# USB2TTL.net
KiCad netlist of a schematic drawn in Altium Designer
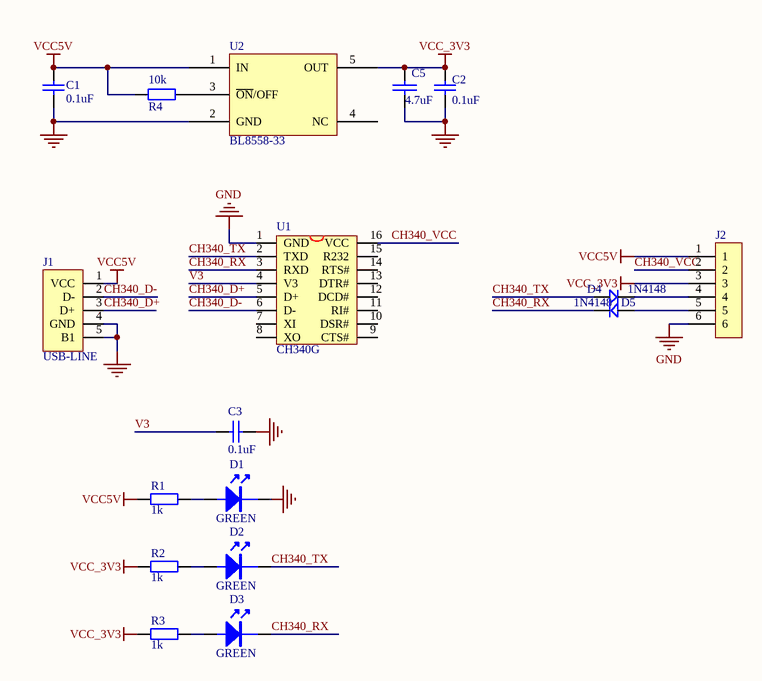
[diagram p0: USB2TTL.SchDoc]

(export (version "E")
  (design (tool "Eeschema 10.0.6"))
  (components
    (comp (ref "C1")
      (value "0.1uF")
      (footprint "FT_0603_C")
      (description "CAP CER .1UF 16V 10% X7R 0603")
      (fields
        (field (name "PART NUMBER") "GRM188R71C104KA01D")
        (field (name "MANUFACTURER") "Murata Electronics North America")
      )
      (libsource (lib "Altium_SVN_Library") (part "Capacitor"))
    )
    (comp (ref "C2")
      (value "0.1uF")
      (footprint "FT_0603_C")
      (description "CAP CER .1UF 16V 10% X7R 0603")
      (fields
        (field (name "PART NUMBER") "GRM188R71C104KA01D")
        (field (name "MANUFACTURER") "Murata Electronics North America")
      )
      (libsource (lib "Altium_SVN_Library") (part "Capacitor"))
    )
    (comp (ref "C3")
      (value "0.1uF")
      (footprint "FT_0603_C")
      (description "CAP CER .1UF 16V 10% X7R 0603")
      (fields
        (field (name "PART NUMBER") "GRM188R71C104KA01D")
        (field (name "MANUFACTURER") "Murata Electronics North America")
      )
      (libsource (lib "Altium_SVN_Library") (part "Capacitor"))
    )
    (comp (ref "C5")
      (value "4.7uF")
      (footprint "FT_0805_C")
      (description "Capacitor")
      (libsource (lib "*") (part "CAP"))
    )
    (comp (ref "D1") (value "GREEN") (footprint "FT_0603_D") (libsource (lib "FTSCH") (part "LED")))
    (comp (ref "D2") (value "GREEN") (footprint "FT_0603_D") (libsource (lib "FTSCH") (part "LED")))
    (comp (ref "D3") (value "GREEN") (footprint "FT_0603_D") (libsource (lib "FTSCH") (part "LED")))
    (comp (ref "D4") (value "1N4148") (footprint "DIODE_SOP") (libsource (lib "WARSHIP") (part "D")))
    (comp (ref "D5") (value "1N4148") (footprint "DIODE_SOP") (libsource (lib "WARSHIP") (part "D")))
    (comp (ref "J1")
      (value "USB-LINE")
      (footprint "FT_USBIF_Micro_BT_CB")
      (libsource (lib "USB转TTL") (part "USB-LINE"))
    )
    (comp (ref "J2") (value "CON6") (footprint "HDR1X6") (libsource (lib "FTSCH") (part "CON6")))
    (comp (ref "R1")
      (value "1k")
      (footprint "FT_0603_R")
      (description "RES 1.0M OHM 1/10W 5% 0603 SMD")
      (fields (field (name "PART NUMBER") "RC0603JR-071ML") (field (name "MANUFACTURER") "Yageo"))
      (libsource (lib "*") (part "Resistor"))
    )
    (comp (ref "R2")
      (value "1k")
      (footprint "FT_0603_R")
      (description "RES 1.0M OHM 1/10W 5% 0603 SMD")
      (fields (field (name "PART NUMBER") "RC0603JR-071ML") (field (name "MANUFACTURER") "Yageo"))
      (libsource (lib "*") (part "Resistor"))
    )
    (comp (ref "R3")
      (value "1k")
      (footprint "FT_0603_R")
      (description "RES 1.0M OHM 1/10W 5% 0603 SMD")
      (fields (field (name "PART NUMBER") "RC0603JR-071ML") (field (name "MANUFACTURER") "Yageo"))
      (libsource (lib "*") (part "Resistor"))
    )
    (comp (ref "R4")
      (value "10k")
      (footprint "FT_0603_R")
      (description "RES 1.0M OHM 1/10W 5% 0603 SMD")
      (fields (field (name "PART NUMBER") "RC0603JR-071ML") (field (name "MANUFACTURER") "Yageo"))
      (libsource (lib "*") (part "Resistor"))
    )
    (comp (ref "U1")
      (value "CH340G")
      (footprint "SOP16M")
      (description "USB2UART")
      (libsource (lib "WARSHIP") (part "CH340G"))
    )
    (comp (ref "U2") (value "BL8558-33") (footprint "FT_SOT-23-5") (libsource (lib "FTSCH") (part "LDO_5")))
  )
  (nets
    (net (code "1") (name "/CH340_D+") (class "Default")
      (node (ref "J1") (pin "3") (pinfunction "D+_3") (pintype "passive"))
      (node (ref "U1") (pin "5") (pinfunction "D+_5") (pintype "passive"))
    )
    (net (code "2") (name "/CH340_D-") (class "Default")
      (node (ref "J1") (pin "2") (pinfunction "D-_2") (pintype "passive"))
      (node (ref "U1") (pin "6") (pinfunction "D-_6") (pintype "passive"))
    )
    (net (code "3") (name "/CH340_RX") (class "Default")
      (node (ref "D3") (pin "2") (pinfunction "2_2") (pintype "passive"))
      (node (ref "D5") (pin "2") (pintype "passive"))
      (node (ref "U1") (pin "3") (pinfunction "RXD_3") (pintype "passive"))
    )
    (net (code "4") (name "/CH340_TX") (class "Default")
      (node (ref "D2") (pin "2") (pinfunction "2_2") (pintype "passive"))
      (node (ref "D4") (pin "1") (pintype "passive"))
      (node (ref "U1") (pin "2") (pinfunction "TXD_2") (pintype "passive"))
    )
    (net (code "5") (name "/CH340_VCC") (class "Default")
      (node (ref "J2") (pin "2") (pinfunction "2_2") (pintype "passive"))
      (node (ref "U1") (pin "16") (pinfunction "VCC_16") (pintype "passive"))
    )
    (net (code "6") (name "/V3") (class "Default")
      (node (ref "C3") (pin "2") (pinfunction "2_2") (pintype "passive"))
      (node (ref "U1") (pin "4") (pinfunction "V3_4") (pintype "passive"))
    )
    (net (code "7") (name "<NO NET>") (class "Default")
      (node (ref "C3") (pin "1") (pinfunction "1_1") (pintype "passive"))
    )
    (net (code "8") (name "GND") (class "Default")
      (node (ref "C1") (pin "1") (pinfunction "1_1") (pintype "passive"))
      (node (ref "C2") (pin "1") (pinfunction "1_1") (pintype "passive"))
      (node (ref "C5") (pin "1") (pinfunction "1_1") (pintype "passive"))
      (node (ref "D1") (pin "2") (pinfunction "2_2") (pintype "passive"))
      (node (ref "J1") (pin "4") (pinfunction "GND_4") (pintype "passive"))
      (node (ref "J1") (pin "5") (pinfunction "B1_5") (pintype "passive"))
      (node (ref "J2") (pin "6") (pinfunction "6_6") (pintype "passive"))
      (node (ref "U1") (pin "1") (pinfunction "GND_1") (pintype "passive"))
      (node (ref "U2") (pin "2") (pinfunction "GND_2") (pintype "power_in"))
    )
    (net (code "9") (name "Net-(D1-Pad1)") (class "Default")
      (node (ref "D1") (pin "1") (pinfunction "1_1") (pintype "passive"))
      (node (ref "R1") (pin "2") (pinfunction "2_2") (pintype "passive"))
    )
    (net (code "10") (name "Net-(D2-Pad1)") (class "Default")
      (node (ref "D2") (pin "1") (pinfunction "1_1") (pintype "passive"))
      (node (ref "R2") (pin "2") (pinfunction "2_2") (pintype "passive"))
    )
    (net (code "11") (name "Net-(D3-Pad1)") (class "Default")
      (node (ref "D3") (pin "1") (pinfunction "1_1") (pintype "passive"))
      (node (ref "R3") (pin "2") (pinfunction "2_2") (pintype "passive"))
    )
    (net (code "12") (name "Net-(D4-Pad2)") (class "Default")
      (node (ref "D4") (pin "2") (pintype "passive"))
      (node (ref "J2") (pin "4") (pinfunction "4_4") (pintype "passive"))
    )
    (net (code "13") (name "Net-(D5-Pad1)") (class "Default")
      (node (ref "D5") (pin "1") (pintype "passive"))
      (node (ref "J2") (pin "5") (pinfunction "5_5") (pintype "passive"))
    )
    (net (code "14") (name "Net-(U2-~{ON}{slash}OFF)") (class "Default")
      (node (ref "R4") (pin "2") (pinfunction "2_2") (pintype "passive"))
      (node (ref "U2") (pin "3") (pinfunction "~{ON}/OFF_3") (pintype "passive"))
    )
    (net (code "15") (name "VCC5V") (class "Default")
      (node (ref "C1") (pin "2") (pinfunction "2_2") (pintype "passive"))
      (node (ref "J1") (pin "1") (pinfunction "VCC_1") (pintype "passive"))
      (node (ref "J2") (pin "1") (pinfunction "1_1") (pintype "passive"))
      (node (ref "R1") (pin "1") (pinfunction "1_1") (pintype "passive"))
      (node (ref "R4") (pin "1") (pinfunction "1_1") (pintype "passive"))
      (node (ref "U2") (pin "1") (pinfunction "IN_1") (pintype "power_in"))
    )
    (net (code "16") (name "VCC_3V3") (class "Default")
      (node (ref "C2") (pin "2") (pinfunction "2_2") (pintype "passive"))
      (node (ref "C5") (pin "2") (pinfunction "2_2") (pintype "passive"))
      (node (ref "J2") (pin "3") (pinfunction "3_3") (pintype "passive"))
      (node (ref "R2") (pin "1") (pinfunction "1_1") (pintype "passive"))
      (node (ref "R3") (pin "1") (pinfunction "1_1") (pintype "passive"))
      (node (ref "U2") (pin "5") (pinfunction "OUT_5") (pintype "power_in"))
    )
    (net (code "17") (name "unconnected-(U1-CTS#-Pad9)") (class "Default")
      (node (ref "U1") (pin "9") (pinfunction "CTS#_9") (pintype "passive"))
    )
    (net (code "18") (name "unconnected-(U1-DCD#-Pad12)") (class "Default")
      (node (ref "U1") (pin "12") (pinfunction "DCD#_12") (pintype "passive"))
    )
    (net (code "19") (name "unconnected-(U1-DSR#-Pad10)") (class "Default")
      (node (ref "U1") (pin "10") (pinfunction "DSR#_10") (pintype "passive"))
    )
    (net (code "20") (name "unconnected-(U1-DTR#-Pad13)") (class "Default")
      (node (ref "U1") (pin "13") (pinfunction "DTR#_13") (pintype "passive"))
    )
    (net (code "21") (name "unconnected-(U1-R232-Pad15)") (class "Default")
      (node (ref "U1") (pin "15") (pinfunction "R232_15") (pintype "passive"))
    )
    (net (code "22") (name "unconnected-(U1-RI#-Pad11)") (class "Default")
      (node (ref "U1") (pin "11") (pinfunction "RI#_11") (pintype "passive"))
    )
    (net (code "23") (name "unconnected-(U1-RTS#-Pad14)") (class "Default")
      (node (ref "U1") (pin "14") (pinfunction "RTS#_14") (pintype "passive"))
    )
    (net (code "24") (name "unconnected-(U1-XI-Pad7)") (class "Default")
      (node (ref "U1") (pin "7") (pinfunction "XI_7") (pintype "passive"))
    )
    (net (code "25") (name "unconnected-(U1-XO-Pad8)") (class "Default")
      (node (ref "U1") (pin "8") (pinfunction "XO_8") (pintype "passive"))
    )
    (net (code "26") (name "unconnected-(U2-NC-Pad4)") (class "Default")
      (node (ref "U2") (pin "4") (pinfunction "NC_4") (pintype "passive"))
    )
  )
)
